# TREMONE.net
KiCad netlist of a schematic drawn in EAGLE
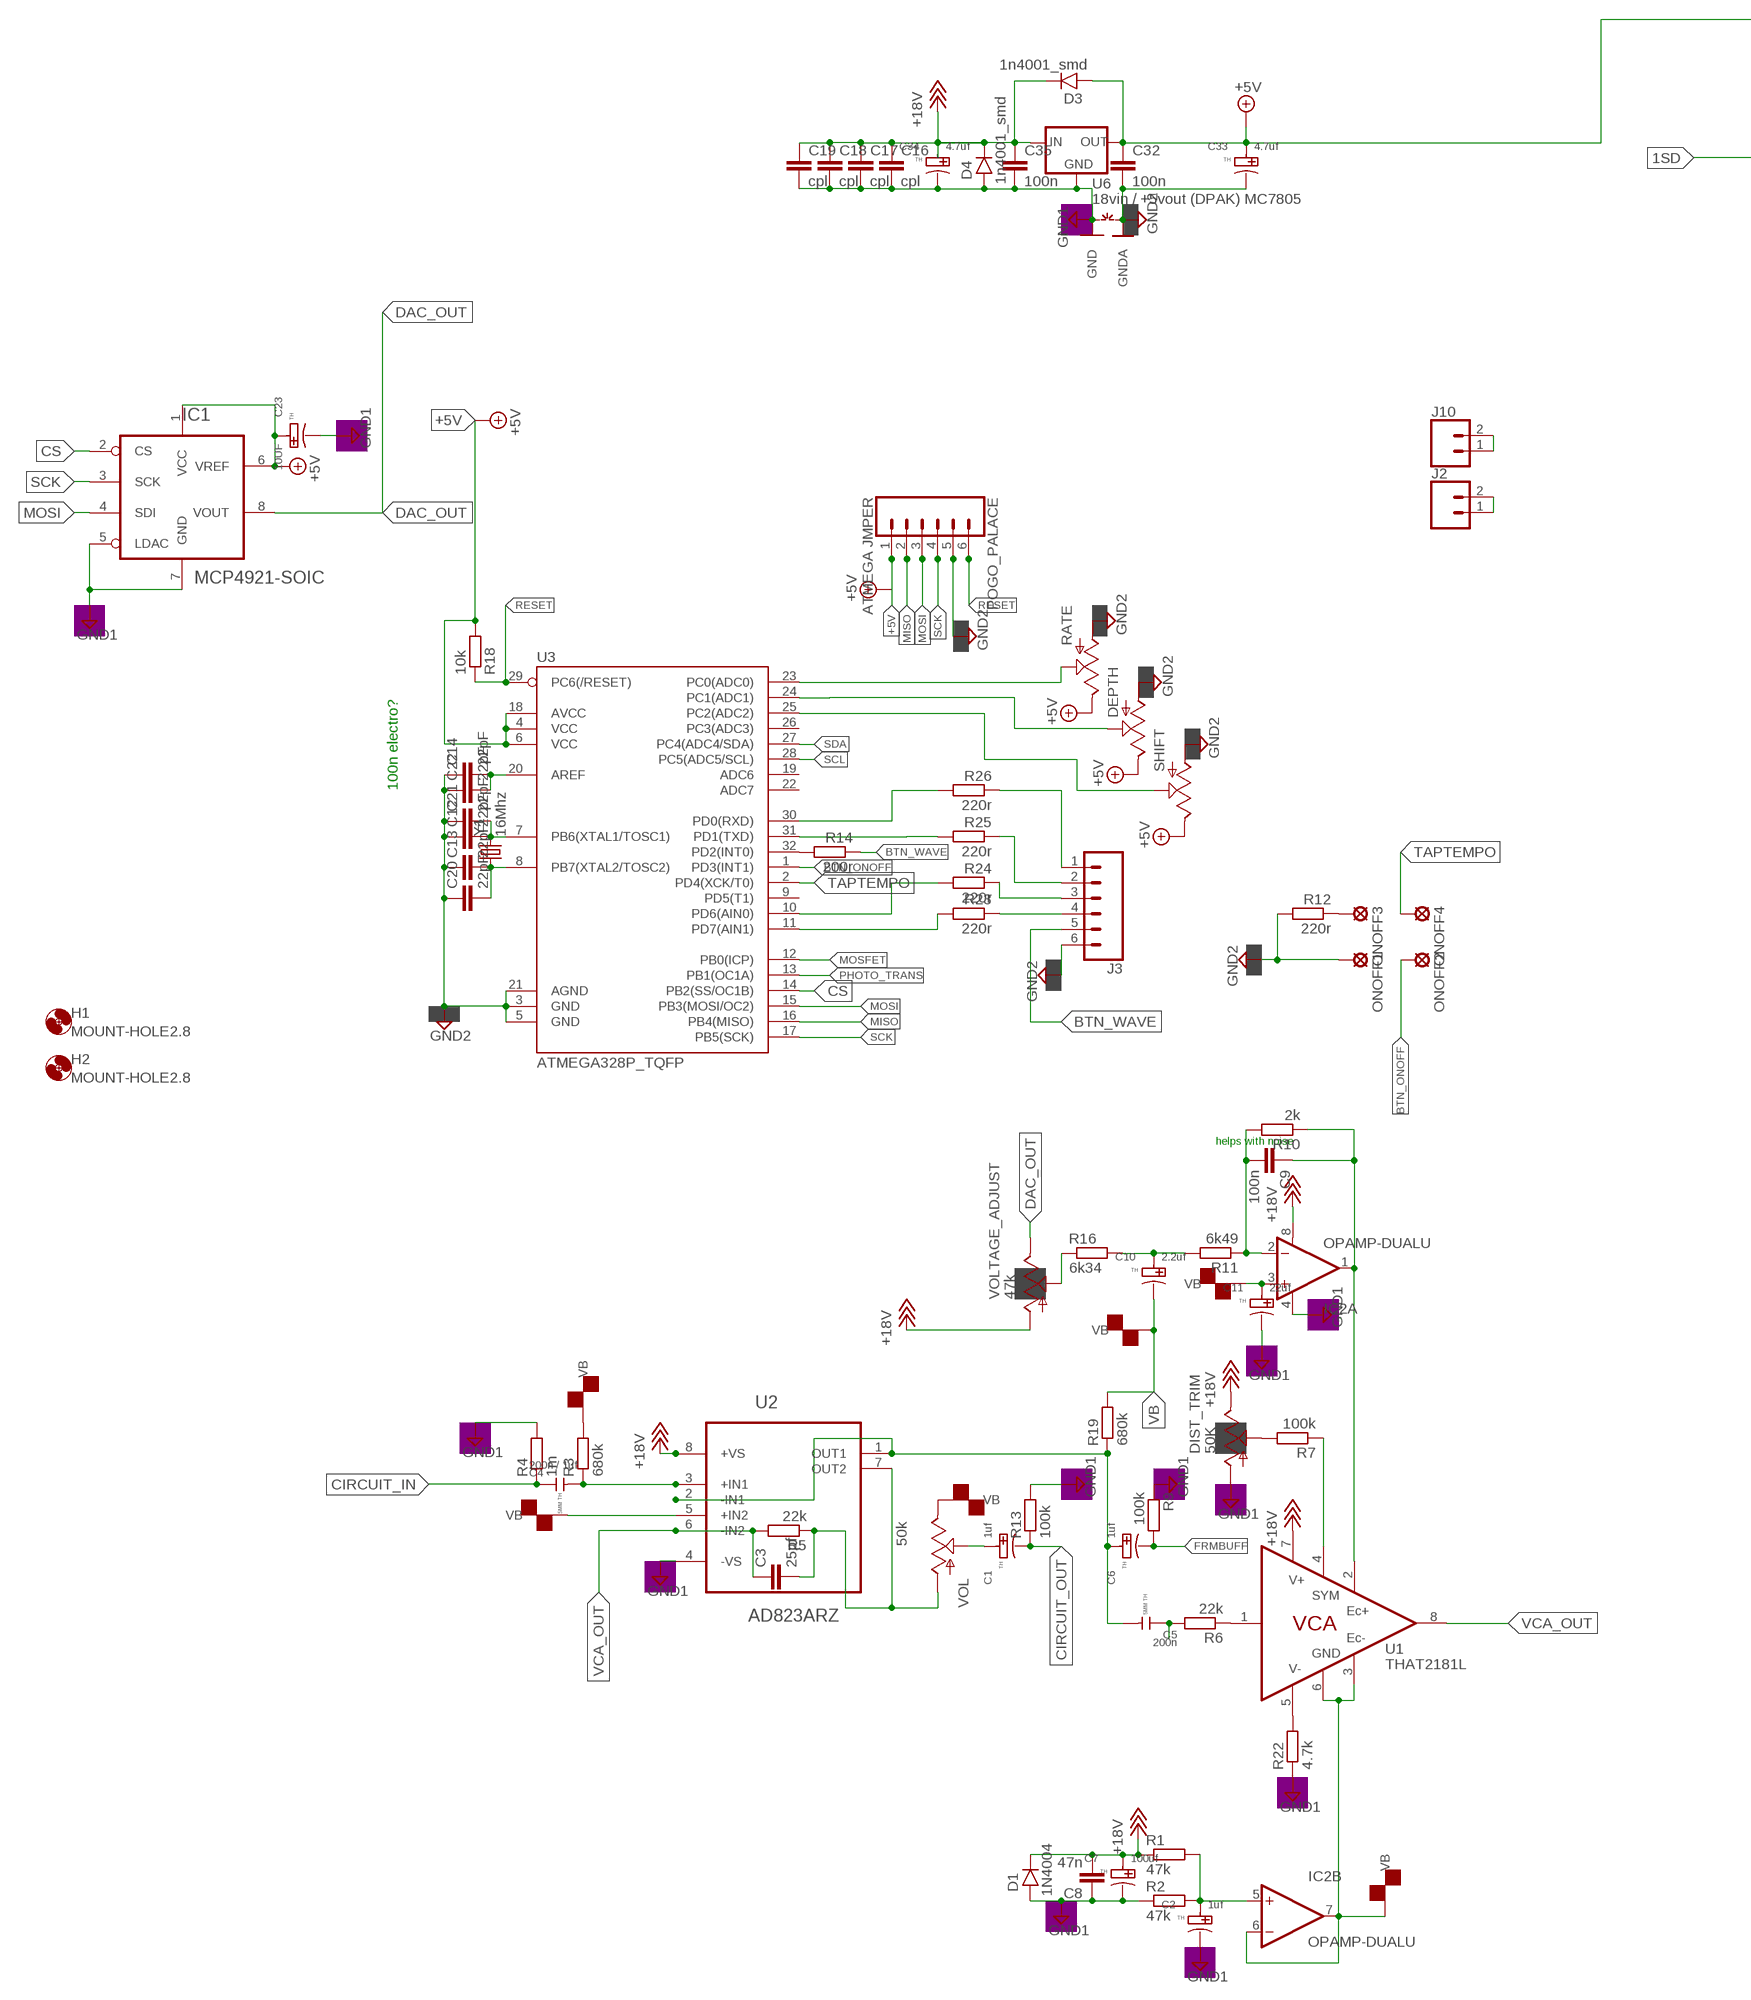
[diagram p0: schematic, sheet 1, part 1 of 2]
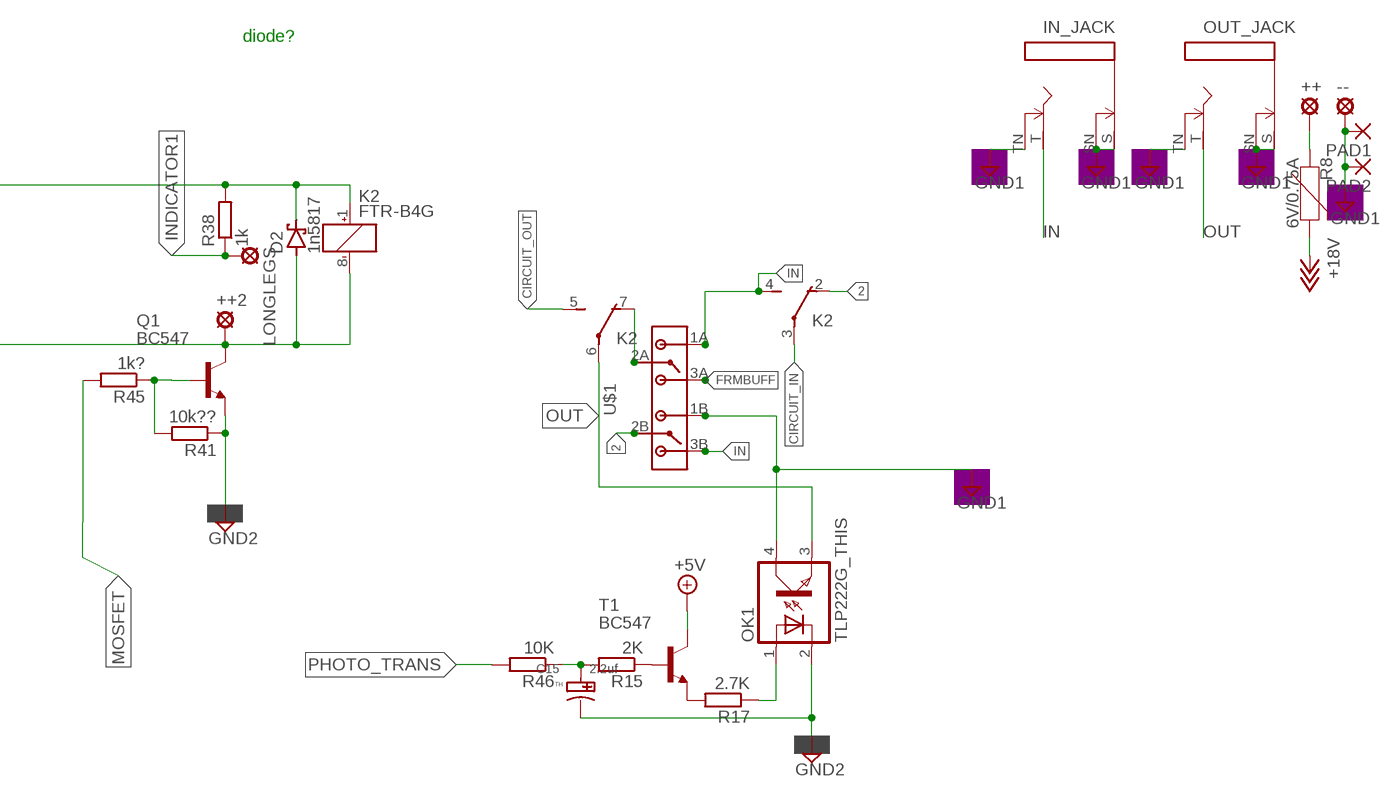
[diagram p1: schematic, sheet 1, part 2 of 2]

(export (version "E")
  (design (tool "Eeschema 10.0.6"))
  (components
    (comp (ref "++")
      (value "LSP10")
      (footprint "eagle-import:LSP10")
      (libsource (lib "eagle-import") (part "LSP10"))
    )
    (comp (ref "++2")
      (value "LSP10")
      (footprint "eagle-import:LSP10")
      (libsource (lib "eagle-import") (part "LSP10"))
    )
    (comp (ref "--")
      (value "LSP10")
      (footprint "eagle-import:LSP10")
      (libsource (lib "eagle-import") (part "LSP10"))
    )
    (comp (ref "C1")
      (value "1uf")
      (footprint "eagle-import:PC-D5.3MM")
      (fields (field (name "PACKAGE") "TH"))
      (libsource (lib "eagle-import") (part "THRU-HOLE-POLARIZED"))
    )
    (comp (ref "C2")
      (value "1uf")
      (footprint "eagle-import:PC-D5.3MM")
      (fields (field (name "PACKAGE") "TH"))
      (libsource (lib "eagle-import") (part "THRU-HOLE-POLARIZED"))
    )
    (comp (ref "C3")
      (value "25pf")
      (footprint "eagle-import:C1206")
      (libsource (lib "eagle-import") (part "C-EUC1206"))
    )
    (comp (ref "C4")
      (value "200n / 1uf")
      (footprint "eagle-import:CERAMIC-5MM")
      (fields (field (name "PACKAGE") "5MM TH"))
      (libsource (lib "eagle-import") (part "THRU_HOLE_5MM_SPACING"))
    )
    (comp (ref "C5")
      (value "200n")
      (footprint "eagle-import:CERAMIC-5MM")
      (fields (field (name "PACKAGE") "5MM TH"))
      (libsource (lib "eagle-import") (part "THRU_HOLE_5MM_SPACING"))
    )
    (comp (ref "C6")
      (value "1uf")
      (footprint "eagle-import:PC-D5.3MM")
      (fields (field (name "PACKAGE") "TH"))
      (libsource (lib "eagle-import") (part "THRU-HOLE-POLARIZED"))
    )
    (comp (ref "C7")
      (value "100uf")
      (footprint "eagle-import:PC-D5.3MM")
      (fields (field (name "PACKAGE") "TH"))
      (libsource (lib "eagle-import") (part "THRU-HOLE-POLARIZED"))
    )
    (comp (ref "C8")
      (value "47n")
      (footprint "eagle-import:C1206")
      (libsource (lib "eagle-import") (part "C-EUC1206"))
    )
    (comp (ref "C9")
      (value "100n")
      (footprint "eagle-import:C1206")
      (libsource (lib "eagle-import") (part "C-EUC1206"))
    )
    (comp (ref "C10")
      (value "2.2uf")
      (footprint "eagle-import:PC-D5.3MM")
      (fields (field (name "PACKAGE") "TH"))
      (libsource (lib "eagle-import") (part "THRU-HOLE-POLARIZED"))
    )
    (comp (ref "C11")
      (value "22uf")
      (footprint "eagle-import:PC-D5.3MM")
      (fields (field (name "PACKAGE") "TH"))
      (libsource (lib "eagle-import") (part "THRU-HOLE-POLARIZED"))
    )
    (comp (ref "C12")
      (value "22pF")
      (footprint "eagle-import:0603")
      (libsource (lib "eagle-import") (part "22PF-0603-50V-5%"))
    )
    (comp (ref "C13")
      (value "22pF")
      (footprint "eagle-import:0603")
      (libsource (lib "eagle-import") (part "22PF-0603-50V-5%"))
    )
    (comp (ref "C14")
      (value "22pF")
      (footprint "eagle-import:CAP-PTH-2.54")
      (libsource (lib "eagle-import") (part "22PF-PTH-2.54MM-200V-5%"))
    )
    (comp (ref "C15")
      (value "2.2uf")
      (footprint "eagle-import:PC-D5.3MM")
      (fields (field (name "PACKAGE") "TH"))
      (libsource (lib "eagle-import") (part "THRU-HOLE-POLARIZED"))
    )
    (comp (ref "C16")
      (value "cpl")
      (footprint "eagle-import:C1206")
      (libsource (lib "eagle-import") (part "resistor_348_C-EUC1206"))
    )
    (comp (ref "C17")
      (value "cpl")
      (footprint "eagle-import:C1206")
      (libsource (lib "eagle-import") (part "resistor_348_C-EUC1206"))
    )
    (comp (ref "C18")
      (value "cpl")
      (footprint "eagle-import:C1206")
      (libsource (lib "eagle-import") (part "resistor_348_C-EUC1206"))
    )
    (comp (ref "C19")
      (value "cpl")
      (footprint "eagle-import:C1206")
      (libsource (lib "eagle-import") (part "resistor_348_C-EUC1206"))
    )
    (comp (ref "C20")
      (value "22pF")
      (footprint "eagle-import:CAP-PTH-2.54")
      (libsource (lib "eagle-import") (part "22PF-PTH-2.54MM-200V-5%"))
    )
    (comp (ref "C21")
      (value "22pF")
      (footprint "eagle-import:CAP-PTH-2.54")
      (libsource (lib "eagle-import") (part "22PF-PTH-2.54MM-200V-5%"))
    )
    (comp (ref "C22")
      (value "22pF")
      (footprint "eagle-import:0603")
      (libsource (lib "eagle-import") (part "22PF-0603-50V-5%"))
    )
    (comp (ref "C23")
      (value "10UF")
      (footprint "eagle-import:PC-D5.3MM")
      (fields (field (name "PACKAGE") "TH"))
      (libsource (lib "eagle-import") (part "THRU-HOLE-POLARIZED"))
    )
    (comp (ref "C32")
      (value "100n")
      (footprint "eagle-import:C1206")
      (libsource (lib "eagle-import") (part "resistor_348_C-EUC1206"))
    )
    (comp (ref "C33")
      (value "4.7uf")
      (footprint "eagle-import:PC-D5.3MM")
      (fields (field (name "PACKAGE") "TH"))
      (libsource (lib "eagle-import") (part "THRU-HOLE-POLARIZED"))
    )
    (comp (ref "C34")
      (value "4.7uf")
      (footprint "eagle-import:PC-D5.3MM")
      (fields (field (name "PACKAGE") "TH"))
      (libsource (lib "eagle-import") (part "THRU-HOLE-POLARIZED"))
    )
    (comp (ref "C35")
      (value "100n")
      (footprint "eagle-import:C1206")
      (libsource (lib "eagle-import") (part "resistor_348_C-EUC1206"))
    )
    (comp (ref "D1")
      (value "1N4004")
      (footprint "eagle-import:DO41-1")
      (libsource (lib "eagle-import") (part "1N400X.1"))
    )
    (comp (ref "D2")
      (value "1n5817")
      (footprint "eagle-import:SMB")
      (libsource (lib "eagle-import") (part "SCHOTTKY-DIODESMD"))
    )
    (comp (ref "D3")
      (value "1n4001_smd")
      (footprint "eagle-import:DO41-1")
      (libsource (lib "eagle-import") (part "1N400X.1"))
    )
    (comp (ref "D4")
      (value "1n4001_smd")
      (footprint "eagle-import:DO41-1")
      (libsource (lib "eagle-import") (part "1N400X.1"))
    )
    (comp (ref "DEPTH")
      (value "POT")
      (footprint "eagle-import:ALPS_POT")
      (libsource (lib "eagle-import") (part "POT"))
    )
    (comp (ref "DIST_TRIM")
      (value "50K")
      (footprint "eagle-import:3223G")
      (libsource (lib "eagle-import") (part "TRIM_US-3223G"))
    )
    (comp (ref "H1")
      (value "MOUNT-HOLE2.8")
      (footprint "eagle-import:2,8")
      (libsource (lib "eagle-import") (part "MOUNT-HOLE2.8"))
    )
    (comp (ref "H2")
      (value "MOUNT-HOLE2.8")
      (footprint "eagle-import:2,8")
      (libsource (lib "eagle-import") (part "MOUNT-HOLE2.8"))
    )
    (comp (ref "IC1")
      (value "MCP4921-SOIC")
      (footprint "eagle-import:SOIC-8")
      (libsource (lib "eagle-import") (part "MCP491-SOIC2"))
    )
    (comp (ref "IC2")
      (value "OPAMP-DUALU")
      (footprint "eagle-import:SO08")
      (libsource (lib "eagle-import") (part "OPAMP-DUALU"))
    )
    (comp (ref "IN_JACK")
      (value "MMMONNNNOHOLES")
      (footprint "eagle-import:MONONOHOLES")
      (libsource (lib "eagle-import") (part "MMMONNNNOHOLES"))
    )
    (comp (ref "J2")
      (value "CONN_02PTH3")
      (footprint "eagle-import:1X02_LONGPADS")
      (libsource (lib "eagle-import") (part "CONN_02PTH3"))
    )
    (comp (ref "J3")
      (value "CONN_06NO_SILK_FEMALE_PTH")
      (footprint "eagle-import:1X06_NO_SILK")
      (libsource (lib "eagle-import") (part "CONN_06NO_SILK_FEMALE_PTH"))
    )
    (comp (ref "J10")
      (value "CONN_02PTH3")
      (footprint "eagle-import:1X02_LONGPADS")
      (libsource (lib "eagle-import") (part "CONN_02PTH3"))
    )
    (comp (ref "K2")
      (value "FTR-B4G")
      (footprint "eagle-import:FTR-B4G")
      (libsource (lib "eagle-import") (part "FTR-B4G"))
    )
    (comp (ref "LONGLEGS")
      (value "LSP10")
      (footprint "eagle-import:LSP10")
      (libsource (lib "eagle-import") (part "LSP10"))
    )
    (comp (ref "OK1")
      (value "TLP222G_THIS")
      (footprint "eagle-import:DIL04")
      (libsource (lib "eagle-import") (part "TLP222G_THIS"))
    )
    (comp (ref "ONOFF1")
      (value "LSP10")
      (footprint "eagle-import:LSP10")
      (libsource (lib "eagle-import") (part "LSP10"))
    )
    (comp (ref "ONOFF2")
      (value "LSP10")
      (footprint "eagle-import:LSP10")
      (libsource (lib "eagle-import") (part "LSP10"))
    )
    (comp (ref "ONOFF3")
      (value "LSP10")
      (footprint "eagle-import:LSP10")
      (libsource (lib "eagle-import") (part "LSP10"))
    )
    (comp (ref "ONOFF4")
      (value "LSP10")
      (footprint "eagle-import:LSP10")
      (libsource (lib "eagle-import") (part "LSP10"))
    )
    (comp (ref "OUT_JACK")
      (value "MMMONNNNOHOLES")
      (footprint "eagle-import:MONONOHOLES")
      (libsource (lib "eagle-import") (part "MMMONNNNOHOLES"))
    )
    (comp (ref "PAD1")
      (value "SMD5")
      (footprint "eagle-import:SMD2,54-5,08")
      (libsource (lib "eagle-import") (part "SMD5"))
    )
    (comp (ref "PAD2")
      (value "SMD5")
      (footprint "eagle-import:SMD2,54-5,08")
      (libsource (lib "eagle-import") (part "SMD5"))
    )
    (comp (ref "POGO_PALACE")
      (value "ATMEGA JMPER")
      (footprint "eagle-import:1X06_LONGPADS")
      (libsource (lib "eagle-import") (part "CONN_06LONGPADS"))
    )
    (comp (ref "Q1")
      (value "BC547")
      (footprint "eagle-import:TO92")
      (libsource (lib "eagle-import") (part "BC547"))
    )
    (comp (ref "R1")
      (value "47k")
      (footprint "eagle-import:M1206")
      (libsource (lib "eagle-import") (part "R-EU_M1206"))
    )
    (comp (ref "R2")
      (value "47k")
      (footprint "eagle-import:M1206")
      (libsource (lib "eagle-import") (part "R-EU_M1206"))
    )
    (comp (ref "R3")
      (value "680k")
      (footprint "eagle-import:M1206")
      (libsource (lib "eagle-import") (part "R-EU_M1206"))
    )
    (comp (ref "R4")
      (value "1m")
      (footprint "eagle-import:M1206")
      (libsource (lib "eagle-import") (part "R-EU_M1206"))
    )
    (comp (ref "R5")
      (value "22k")
      (footprint "eagle-import:M1206")
      (libsource (lib "eagle-import") (part "R-EU_M1206"))
    )
    (comp (ref "R6")
      (value "22k")
      (footprint "eagle-import:M1206")
      (libsource (lib "eagle-import") (part "R-EU_M1206"))
    )
    (comp (ref "R7")
      (value "100k")
      (footprint "eagle-import:M1206")
      (libsource (lib "eagle-import") (part "R-EU_M1206"))
    )
    (comp (ref "R8")
      (value "6V/0.75A")
      (footprint "eagle-import:1206")
      (libsource (lib "eagle-import") (part "PPTC_THREE-QUARTER-AMP"))
    )
    (comp (ref "R9")
      (value "100k")
      (footprint "eagle-import:M1206")
      (libsource (lib "eagle-import") (part "R-EU_M1206"))
    )
    (comp (ref "R10")
      (value "2k")
      (footprint "eagle-import:M1206")
      (libsource (lib "eagle-import") (part "R-EU_M1206"))
    )
    (comp (ref "R11")
      (value "6k49")
      (footprint "eagle-import:M1206")
      (libsource (lib "eagle-import") (part "R-EU_M1206"))
    )
    (comp (ref "R12")
      (value "220r")
      (footprint "eagle-import:M1206")
      (libsource (lib "eagle-import") (part "R-EU_M1206"))
    )
    (comp (ref "R13")
      (value "100k")
      (footprint "eagle-import:M1206")
      (libsource (lib "eagle-import") (part "R-EU_M1206"))
    )
    (comp (ref "R14")
      (value "200r")
      (footprint "eagle-import:M1206")
      (libsource (lib "eagle-import") (part "R-EU_M1206"))
    )
    (comp (ref "R15")
      (value "2K")
      (footprint "eagle-import:M1206")
      (libsource (lib "eagle-import") (part "resistor_348_R-EU_M1206"))
    )
    (comp (ref "R16")
      (value "6k34")
      (footprint "eagle-import:M1206")
      (libsource (lib "eagle-import") (part "R-EU_M1206"))
    )
    (comp (ref "R17")
      (value "2.7K")
      (footprint "eagle-import:M1206")
      (libsource (lib "eagle-import") (part "resistor_348_R-EU_M1206"))
    )
    (comp (ref "R18")
      (value "10k")
      (footprint "eagle-import:M1206")
      (libsource (lib "eagle-import") (part "R-EU_M1206"))
    )
    (comp (ref "R19")
      (value "680k")
      (footprint "eagle-import:M1206")
      (libsource (lib "eagle-import") (part "R-EU_M1206"))
    )
    (comp (ref "R22")
      (value "4.7k")
      (footprint "eagle-import:M1206")
      (libsource (lib "eagle-import") (part "R-EU_M1206"))
    )
    (comp (ref "R23")
      (value "220r")
      (footprint "eagle-import:M1206")
      (libsource (lib "eagle-import") (part "R-EU_M1206"))
    )
    (comp (ref "R24")
      (value "220r")
      (footprint "eagle-import:M1206")
      (libsource (lib "eagle-import") (part "R-EU_M1206"))
    )
    (comp (ref "R25")
      (value "220r")
      (footprint "eagle-import:M1206")
      (libsource (lib "eagle-import") (part "R-EU_M1206"))
    )
    (comp (ref "R26")
      (value "220r")
      (footprint "eagle-import:M1206")
      (libsource (lib "eagle-import") (part "R-EU_M1206"))
    )
    (comp (ref "R38")
      (value "1k")
      (footprint "eagle-import:M1206")
      (libsource (lib "eagle-import") (part "resistor_348_R-EU_M1206"))
    )
    (comp (ref "R41")
      (value "10k??")
      (footprint "eagle-import:M1206")
      (libsource (lib "eagle-import") (part "resistor_348_R-EU_M1206"))
    )
    (comp (ref "R45")
      (value "1k?")
      (footprint "eagle-import:M1206")
      (libsource (lib "eagle-import") (part "resistor_348_R-EU_M1206"))
    )
    (comp (ref "R46")
      (value "10K")
      (footprint "eagle-import:M1206")
      (libsource (lib "eagle-import") (part "resistor_348_R-EU_M1206"))
    )
    (comp (ref "RATE")
      (value "POT")
      (footprint "eagle-import:ALPS_POT")
      (libsource (lib "eagle-import") (part "POT"))
    )
    (comp (ref "SHIFT")
      (value "POT")
      (footprint "eagle-import:ALPS_POT")
      (libsource (lib "eagle-import") (part "POT"))
    )
    (comp (ref "T1")
      (value "BC547")
      (footprint "eagle-import:TO92")
      (libsource (lib "eagle-import") (part "transistor_402_BC547"))
    )
    (comp (ref "U$1")
      (value "BYSWITCH")
      (footprint "eagle-import:BUFF_TRBYPASS")
      (libsource (lib "eagle-import") (part "BYSWITCH"))
    )
    (comp (ref "U1")
      (value "THAT2181L")
      (footprint "eagle-import:SIP8")
      (libsource (lib "eagle-import") (part "THAT2181L"))
    )
    (comp (ref "U2")
      (value "AD823ARZ")
      (footprint "eagle-import:SOIC127P600X175-8N")
      (libsource (lib "eagle-import") (part "AD823ARZ"))
    )
    (comp (ref "U3")
      (value "ATMEGA328P_TQFP")
      (footprint "eagle-import:TQFP32-08")
      (libsource (lib "eagle-import") (part "ATMEGA328P_TQFP"))
    )
    (comp (ref "U6")
      (value "18vin / +5vout (DPAK) MC7805")
      (footprint "eagle-import:TO-252")
      (libsource (lib "eagle-import") (part "V_REG_78XX7812"))
    )
    (comp (ref "VOL")
      (value "50k")
      (footprint "eagle-import:ALPS_POT")
      (libsource (lib "eagle-import") (part "POT"))
    )
    (comp (ref "VOLTAGE_ADJUST")
      (value "47k")
      (footprint "eagle-import:3223G")
      (libsource (lib "eagle-import") (part "TRIM_US-3223G"))
    )
    (comp (ref "Y1")
      (value "16Mhz")
      (footprint "eagle-import:HC49US")
      (libsource (lib "eagle-import") (part "CRYSTALHC49US"))
    )
    (comp (ref "~NUDEV~1")
      (value "GND-GNDA1,27MM")
      (footprint "eagle-import:GND-GNDA-1,27MM")
      (libsource (lib "eagle-import") (part "GND-GNDA1,27MM"))
    )
  )
  (nets
    (net (code "1") (name "+5V") (class "Default")
      (node (ref "C23") (pin "+") (pinfunction "+_+") (pintype "passive"))
      (node (ref "C32") (pin "1") (pinfunction "1_1") (pintype "passive"))
      (node (ref "C33") (pin "+") (pinfunction "+_+") (pintype "passive"))
      (node (ref "D2") (pin "C") (pinfunction "C_C") (pintype "passive"))
      (node (ref "D3") (pin "A") (pinfunction "A_A") (pintype "passive"))
      (node (ref "DEPTH") (pin "P$1") (pinfunction "E_P$1") (pintype "passive"))
      (node (ref "IC1") (pin "1") (pinfunction "VCC_1") (pintype "power_in"))
      (node (ref "IC1") (pin "6") (pinfunction "VREF_6") (pintype "input"))
      (node (ref "K2") (pin "1") (pinfunction "+_1") (pintype "passive"))
      (node (ref "POGO_PALACE") (pin "1") (pinfunction "1_1") (pintype "passive"))
      (node (ref "R18") (pin "2") (pinfunction "2_2") (pintype "passive"))
      (node (ref "R38") (pin "2") (pinfunction "2_2") (pintype "passive"))
      (node (ref "RATE") (pin "P$1") (pinfunction "E_P$1") (pintype "passive"))
      (node (ref "SHIFT") (pin "P$1") (pinfunction "E_P$1") (pintype "passive"))
      (node (ref "T1") (pin "3") (pinfunction "C_3") (pintype "passive"))
      (node (ref "U3") (pin "18") (pinfunction "AVCC_18") (pintype "bidirectional"))
      (node (ref "U3") (pin "4") (pinfunction "VCC_4") (pintype "bidirectional"))
      (node (ref "U3") (pin "6") (pinfunction "VCC_6") (pintype "bidirectional"))
      (node (ref "U6") (pin "2") (pinfunction "OUT_2") (pintype "passive"))
    )
    (net (code "2") (name "+18V") (class "Default")
      (node (ref "C16") (pin "1") (pinfunction "1_1") (pintype "passive"))
      (node (ref "C17") (pin "1") (pinfunction "1_1") (pintype "passive"))
      (node (ref "C18") (pin "1") (pinfunction "1_1") (pintype "passive"))
      (node (ref "C19") (pin "1") (pinfunction "1_1") (pintype "passive"))
      (node (ref "C34") (pin "+") (pinfunction "+_+") (pintype "passive"))
      (node (ref "C35") (pin "1") (pinfunction "1_1") (pintype "passive"))
      (node (ref "C7") (pin "+") (pinfunction "+_+") (pintype "passive"))
      (node (ref "C8") (pin "2") (pinfunction "2_2") (pintype "passive"))
      (node (ref "D1") (pin "C") (pinfunction "C_C") (pintype "passive"))
      (node (ref "D3") (pin "C") (pinfunction "C_C") (pintype "passive"))
      (node (ref "D4") (pin "C") (pinfunction "C_C") (pintype "passive"))
      (node (ref "DIST_TRIM") (pin "3") (pinfunction "E_3") (pintype "passive"))
      (node (ref "IC2") (pin "8") (pinfunction "V+_8") (pintype "power_in"))
      (node (ref "R1") (pin "1") (pinfunction "1_1") (pintype "passive"))
      (node (ref "R8") (pin "2") (pinfunction "2_2") (pintype "bidirectional"))
      (node (ref "U1") (pin "7") (pinfunction "V+_7") (pintype "power_in"))
      (node (ref "U2") (pin "8") (pinfunction "+VS_8") (pintype "power_in"))
      (node (ref "U6") (pin "1") (pinfunction "IN_1") (pintype "input"))
      (node (ref "VOLTAGE_ADJUST") (pin "1") (pinfunction "A_1") (pintype "passive"))
    )
    (net (code "3") (name "1SD") (class "Default")
      (node (ref "++2") (pin "MP") (pinfunction "MP_MP") (pintype "passive"))
      (node (ref "D2") (pin "A") (pinfunction "A_A") (pintype "passive"))
      (node (ref "K2") (pin "8") (pinfunction "-_8") (pintype "passive"))
      (node (ref "Q1") (pin "3") (pinfunction "C_3") (pintype "passive"))
    )
    (net (code "4") (name "2") (class "Default")
      (node (ref "K2") (pin "2") (pinfunction "O_2") (pintype "passive"))
      (node (ref "U$1") (pin "2B") (pinfunction "2B_2B") (pintype "passive"))
    )
    (net (code "5") (name "BTN_ONOFF") (class "Default")
      (node (ref "ONOFF2") (pin "MP") (pinfunction "MP_MP") (pintype "passive"))
      (node (ref "U3") (pin "1") (pinfunction "PD3(INT1)_1") (pintype "bidirectional"))
    )
    (net (code "6") (name "BTN_WAVE") (class "Default")
      (node (ref "J3") (pin "5") (pinfunction "5_5") (pintype "passive"))
      (node (ref "R14") (pin "1") (pinfunction "1_1") (pintype "passive"))
    )
    (net (code "7") (name "CIRCUIT_IN") (class "Default")
      (node (ref "C4") (pin "1") (pinfunction "1_1") (pintype "passive"))
      (node (ref "K2") (pin "3") (pinfunction "P_3") (pintype "passive"))
      (node (ref "R4") (pin "1") (pinfunction "1_1") (pintype "passive"))
    )
    (net (code "8") (name "CIRCUIT_OUT") (class "Default")
      (node (ref "C1") (pin "-") (pinfunction "-_-") (pintype "passive"))
      (node (ref "K2") (pin "5") (pinfunction "S_5") (pintype "passive"))
      (node (ref "R13") (pin "1") (pinfunction "1_1") (pintype "passive"))
    )
    (net (code "9") (name "CS") (class "Default")
      (node (ref "IC1") (pin "2") (pinfunction "CS_2") (pintype "input"))
      (node (ref "U3") (pin "14") (pinfunction "PB2(SS/OC1B)_14") (pintype "bidirectional"))
    )
    (net (code "10") (name "DAC_OUT") (class "Default")
      (node (ref "IC1") (pin "8") (pinfunction "VOUT_8") (pintype "output"))
      (node (ref "VOLTAGE_ADJUST") (pin "3") (pinfunction "E_3") (pintype "passive"))
    )
    (net (code "11") (name "FRMBUFF") (class "Default")
      (node (ref "C6") (pin "-") (pinfunction "-_-") (pintype "passive"))
      (node (ref "R9") (pin "2") (pinfunction "2_2") (pintype "passive"))
      (node (ref "U$1") (pin "3A") (pinfunction "3A_3A") (pintype "passive"))
    )
    (net (code "12") (name "GND1") (class "Default")
      (node (ref "--") (pin "MP") (pinfunction "MP_MP") (pintype "passive"))
      (node (ref "C11") (pin "-") (pinfunction "-_-") (pintype "passive"))
      (node (ref "C16") (pin "2") (pinfunction "2_2") (pintype "passive"))
      (node (ref "C17") (pin "2") (pinfunction "2_2") (pintype "passive"))
      (node (ref "C18") (pin "2") (pinfunction "2_2") (pintype "passive"))
      (node (ref "C19") (pin "2") (pinfunction "2_2") (pintype "passive"))
      (node (ref "C2") (pin "-") (pinfunction "-_-") (pintype "passive"))
      (node (ref "C23") (pin "-") (pinfunction "-_-") (pintype "passive"))
      (node (ref "C34") (pin "-") (pinfunction "-_-") (pintype "passive"))
      (node (ref "C35") (pin "2") (pinfunction "2_2") (pintype "passive"))
      (node (ref "C7") (pin "-") (pinfunction "-_-") (pintype "passive"))
      (node (ref "C8") (pin "1") (pinfunction "1_1") (pintype "passive"))
      (node (ref "D1") (pin "A") (pinfunction "A_A") (pintype "passive"))
      (node (ref "D4") (pin "A") (pinfunction "A_A") (pintype "passive"))
      (node (ref "DIST_TRIM") (pin "1") (pinfunction "A_1") (pintype "passive"))
      (node (ref "IC1") (pin "5") (pinfunction "LDAC_5") (pintype "input"))
      (node (ref "IC1") (pin "7") (pinfunction "GND_7") (pintype "power_in"))
      (node (ref "IC2") (pin "4") (pinfunction "V-_4") (pintype "power_in"))
      (node (ref "IN_JACK") (pin "S") (pinfunction "S_S") (pintype "passive"))
      (node (ref "IN_JACK") (pin "SN") (pinfunction "SN_SN") (pintype "passive"))
      (node (ref "IN_JACK") (pin "TN") (pinfunction "TN_TN") (pintype "passive"))
      (node (ref "OK1") (pin "4") (pinfunction "COL_4") (pintype "passive"))
      (node (ref "OUT_JACK") (pin "S") (pinfunction "S_S") (pintype "passive"))
      (node (ref "OUT_JACK") (pin "SN") (pinfunction "SN_SN") (pintype "passive"))
      (node (ref "OUT_JACK") (pin "TN") (pinfunction "TN_TN") (pintype "passive"))
      (node (ref "PAD1") (pin "1") (pinfunction "P_1") (pintype "passive"))
      (node (ref "PAD2") (pin "1") (pinfunction "P_1") (pintype "passive"))
      (node (ref "R13") (pin "2") (pinfunction "2_2") (pintype "passive"))
      (node (ref "R2") (pin "1") (pinfunction "1_1") (pintype "passive"))
      (node (ref "R22") (pin "1") (pinfunction "1_1") (pintype "passive"))
      (node (ref "R4") (pin "2") (pinfunction "2_2") (pintype "passive"))
      (node (ref "R9") (pin "1") (pinfunction "1_1") (pintype "passive"))
      (node (ref "U$1") (pin "1B") (pinfunction "1B_1B") (pintype "passive"))
      (node (ref "U2") (pin "4") (pinfunction "-VS_4") (pintype "power_in"))
      (node (ref "U6") (pin "3") (pinfunction "GND_3") (pintype "input"))
      (node (ref "~NUDEV~1") (pin "GND") (pinfunction "GND_GND") (pintype "power_in"))
    )
    (net (code "13") (name "GND2") (class "Default")
      (node (ref "C12") (pin "1") (pinfunction "1_1") (pintype "passive"))
      (node (ref "C13") (pin "1") (pinfunction "1_1") (pintype "passive"))
      (node (ref "C14") (pin "1") (pinfunction "1_1") (pintype "passive"))
      (node (ref "C15") (pin "-") (pinfunction "-_-") (pintype "passive"))
      (node (ref "C20") (pin "1") (pinfunction "1_1") (pintype "passive"))
      (node (ref "C21") (pin "1") (pinfunction "1_1") (pintype "passive"))
      (node (ref "C22") (pin "1") (pinfunction "1_1") (pintype "passive"))
      (node (ref "C32") (pin "2") (pinfunction "2_2") (pintype "passive"))
      (node (ref "C33") (pin "-") (pinfunction "-_-") (pintype "passive"))
      (node (ref "DEPTH") (pin "P$3") (pinfunction "A_P$3") (pintype "passive"))
      (node (ref "J3") (pin "6") (pinfunction "6_6") (pintype "passive"))
      (node (ref "OK1") (pin "2") (pinfunction "C_2") (pintype "passive"))
      (node (ref "ONOFF1") (pin "MP") (pinfunction "MP_MP") (pintype "passive"))
      (node (ref "POGO_PALACE") (pin "5") (pinfunction "5_5") (pintype "passive"))
      (node (ref "Q1") (pin "1") (pinfunction "E_1") (pintype "passive"))
      (node (ref "R12") (pin "2") (pinfunction "2_2") (pintype "passive"))
      (node (ref "R41") (pin "1") (pinfunction "1_1") (pintype "passive"))
      (node (ref "RATE") (pin "P$3") (pinfunction "A_P$3") (pintype "passive"))
      (node (ref "SHIFT") (pin "P$3") (pinfunction "A_P$3") (pintype "passive"))
      (node (ref "U3") (pin "21") (pinfunction "AGND_21") (pintype "bidirectional"))
      (node (ref "U3") (pin "3") (pinfunction "GND_3") (pintype "bidirectional"))
      (node (ref "U3") (pin "5") (pinfunction "GND_5") (pintype "bidirectional"))
      (node (ref "~NUDEV~1") (pin "GNDA") (pinfunction "GNDA_GNDA") (pintype "power_in"))
    )
    (net (code "14") (name "IN") (class "Default")
      (node (ref "IN_JACK") (pin "T") (pinfunction "T_T") (pintype "passive"))
      (node (ref "K2") (pin "4") (pinfunction "S_4") (pintype "passive"))
      (node (ref "U$1") (pin "1A") (pinfunction "1A_1A") (pintype "passive"))
      (node (ref "U$1") (pin "3B") (pinfunction "3B_3B") (pintype "passive"))
    )
    (net (code "15") (name "INDICATOR1") (class "Default")
      (node (ref "LONGLEGS") (pin "MP") (pinfunction "MP_MP") (pintype "passive"))
      (node (ref "R38") (pin "1") (pinfunction "1_1") (pintype "passive"))
    )
    (net (code "16") (name "MISO") (class "Default")
      (node (ref "POGO_PALACE") (pin "2") (pinfunction "2_2") (pintype "passive"))
      (node (ref "U3") (pin "16") (pinfunction "PB4(MISO)_16") (pintype "bidirectional"))
    )
    (net (code "17") (name "MOSFET") (class "Default")
      (node (ref "R45") (pin "2") (pinfunction "2_2") (pintype "passive"))
      (node (ref "U3") (pin "12") (pinfunction "PB0(ICP)_12") (pintype "bidirectional"))
    )
    (net (code "18") (name "MOSI") (class "Default")
      (node (ref "IC1") (pin "4") (pinfunction "SDI_4") (pintype "input"))
      (node (ref "POGO_PALACE") (pin "3") (pinfunction "3_3") (pintype "passive"))
      (node (ref "U3") (pin "15") (pinfunction "PB3(MOSI/OC2)_15") (pintype "bidirectional"))
    )
    (net (code "19") (name "Net-(++-PadMP)") (class "Default")
      (node (ref "++") (pin "MP") (pinfunction "MP_MP") (pintype "passive"))
      (node (ref "R8") (pin "1") (pinfunction "1_1") (pintype "bidirectional"))
    )
    (net (code "20") (name "Net-(C5-Pad1)") (class "Default")
      (node (ref "C5") (pin "1") (pinfunction "1_1") (pintype "passive"))
      (node (ref "R6") (pin "2") (pinfunction "2_2") (pintype "passive"))
    )
    (net (code "21") (name "Net-(C10-Pad+)") (class "Default")
      (node (ref "C10") (pin "+") (pinfunction "+_+") (pintype "passive"))
      (node (ref "R11") (pin "2") (pinfunction "2_2") (pintype "passive"))
      (node (ref "R16") (pin "2") (pinfunction "2_2") (pintype "passive"))
    )
    (net (code "22") (name "Net-(C15-Pad+)") (class "Default")
      (node (ref "C15") (pin "+") (pinfunction "+_+") (pintype "passive"))
      (node (ref "R15") (pin "2") (pinfunction "2_2") (pintype "passive"))
      (node (ref "R46") (pin "1") (pinfunction "1_1") (pintype "passive"))
    )
    (net (code "23") (name "Net-(DEPTH-S)") (class "Default")
      (node (ref "DEPTH") (pin "P$2") (pinfunction "S_P$2") (pintype "passive"))
      (node (ref "U3") (pin "24") (pinfunction "PC1(ADC1)_24") (pintype "bidirectional"))
    )
    (net (code "24") (name "Net-(DIST_TRIM-S)") (class "Default")
      (node (ref "DIST_TRIM") (pin "2") (pinfunction "S_2") (pintype "passive"))
      (node (ref "R7") (pin "2") (pinfunction "2_2") (pintype "passive"))
    )
    (net (code "25") (name "Net-(IC2A--IN)") (class "Default")
      (node (ref "C9") (pin "2") (pinfunction "2_2") (pintype "passive"))
      (node (ref "IC2") (pin "2") (pinfunction "-IN_2") (pintype "input"))
      (node (ref "R10") (pin "2") (pinfunction "2_2") (pintype "passive"))
      (node (ref "R11") (pin "1") (pinfunction "1_1") (pintype "passive"))
    )
    (net (code "26") (name "Net-(IC2A-OUT)") (class "Default")
      (node (ref "C9") (pin "1") (pinfunction "1_1") (pintype "passive"))
      (node (ref "IC2") (pin "1") (pinfunction "OUT_1") (pintype "output"))
      (node (ref "R10") (pin "1") (pinfunction "1_1") (pintype "passive"))
      (node (ref "U1") (pin "2") (pinfunction "EC+_2") (pintype "passive"))
    )
    (net (code "27") (name "Net-(IC2B-+IN)") (class "Default")
      (node (ref "C2") (pin "+") (pinfunction "+_+") (pintype "passive"))
      (node (ref "IC2") (pin "5") (pinfunction "+IN_5") (pintype "input"))
      (node (ref "R1") (pin "2") (pinfunction "2_2") (pintype "passive"))
      (node (ref "R2") (pin "2") (pinfunction "2_2") (pintype "passive"))
    )
    (net (code "28") (name "Net-(J2-Pad1)") (class "Default")
      (node (ref "J2") (pin "1") (pinfunction "1_1") (pintype "passive"))
      (node (ref "J2") (pin "2") (pinfunction "2_2") (pintype "passive"))
    )
    (net (code "29") (name "Net-(J3-Pad1)") (class "Default")
      (node (ref "J3") (pin "1") (pinfunction "1_1") (pintype "passive"))
      (node (ref "R26") (pin "1") (pinfunction "1_1") (pintype "passive"))
    )
    (net (code "30") (name "Net-(J3-Pad2)") (class "Default")
      (node (ref "J3") (pin "2") (pinfunction "2_2") (pintype "passive"))
      (node (ref "R25") (pin "1") (pinfunction "1_1") (pintype "passive"))
    )
    (net (code "31") (name "Net-(J3-Pad3)") (class "Default")
      (node (ref "J3") (pin "3") (pinfunction "3_3") (pintype "passive"))
      (node (ref "R24") (pin "1") (pinfunction "1_1") (pintype "passive"))
    )
    (net (code "32") (name "Net-(J3-Pad4)") (class "Default")
      (node (ref "J3") (pin "4") (pinfunction "4_4") (pintype "passive"))
      (node (ref "R23") (pin "1") (pinfunction "1_1") (pintype "passive"))
    )
    (net (code "33") (name "Net-(J10-Pad1)") (class "Default")
      (node (ref "J10") (pin "1") (pinfunction "1_1") (pintype "passive"))
      (node (ref "J10") (pin "2") (pinfunction "2_2") (pintype "passive"))
    )
    (net (code "34") (name "Net-(K2B-O)") (class "Default")
      (node (ref "K2") (pin "7") (pinfunction "O_7") (pintype "passive"))
      (node (ref "U$1") (pin "2A") (pinfunction "2A_2A") (pintype "passive"))
    )
    (net (code "35") (name "Net-(OK1-A)") (class "Default")
      (node (ref "OK1") (pin "1") (pinfunction "A_1") (pintype "passive"))
      (node (ref "R17") (pin "1") (pinfunction "1_1") (pintype "passive"))
    )
    (net (code "36") (name "Net-(ONOFF3-PadMP)") (class "Default")
      (node (ref "ONOFF3") (pin "MP") (pinfunction "MP_MP") (pintype "passive"))
      (node (ref "R12") (pin "1") (pinfunction "1_1") (pintype "passive"))
    )
    (net (code "37") (name "Net-(Q1-B)") (class "Default")
      (node (ref "Q1") (pin "2") (pinfunction "B_2") (pintype "passive"))
      (node (ref "R41") (pin "2") (pinfunction "2_2") (pintype "passive"))
      (node (ref "R45") (pin "1") (pinfunction "1_1") (pintype "passive"))
    )
    (net (code "38") (name "Net-(RATE-S)") (class "Default")
      (node (ref "RATE") (pin "P$2") (pinfunction "S_P$2") (pintype "passive"))
      (node (ref "U3") (pin "23") (pinfunction "PC0(ADC0)_23") (pintype "bidirectional"))
    )
    (net (code "39") (name "Net-(SHIFT-S)") (class "Default")
      (node (ref "SHIFT") (pin "P$2") (pinfunction "S_P$2") (pintype "passive"))
      (node (ref "U3") (pin "25") (pinfunction "PC2(ADC2)_25") (pintype "bidirectional"))
    )
    (net (code "40") (name "Net-(T1-B)") (class "Default")
      (node (ref "R15") (pin "1") (pinfunction "1_1") (pintype "passive"))
      (node (ref "T1") (pin "2") (pinfunction "B_2") (pintype "passive"))
    )
    (net (code "41") (name "Net-(T1-E)") (class "Default")
      (node (ref "R17") (pin "2") (pinfunction "2_2") (pintype "passive"))
      (node (ref "T1") (pin "1") (pinfunction "E_1") (pintype "passive"))
    )
    (net (code "42") (name "Net-(U1-IN)") (class "Default")
      (node (ref "R6") (pin "1") (pinfunction "1_1") (pintype "passive"))
      (node (ref "U1") (pin "1") (pinfunction "IN_1") (pintype "input"))
    )
    (net (code "43") (name "Net-(U1-SYM)") (class "Default")
      (node (ref "R7") (pin "1") (pinfunction "1_1") (pintype "passive"))
      (node (ref "U1") (pin "4") (pinfunction "SYM_4") (pintype "passive"))
    )
    (net (code "44") (name "Net-(U1-V-)") (class "Default")
      (node (ref "R22") (pin "2") (pinfunction "2_2") (pintype "passive"))
      (node (ref "U1") (pin "5") (pinfunction "V-_5") (pintype "power_in"))
    )
    (net (code "45") (name "Net-(U2-+IN1)") (class "Default")
      (node (ref "C4") (pin "2") (pinfunction "2_2") (pintype "passive"))
      (node (ref "R3") (pin "1") (pinfunction "1_1") (pintype "passive"))
      (node (ref "U2") (pin "3") (pinfunction "+IN1_3") (pintype "input"))
    )
    (net (code "46") (name "Net-(U2--IN1)") (class "Default")
      (node (ref "C5") (pin "2") (pinfunction "2_2") (pintype "passive"))
      (node (ref "C6") (pin "+") (pinfunction "+_+") (pintype "passive"))
      (node (ref "R19") (pin "1") (pinfunction "1_1") (pintype "passive"))
      (node (ref "U2") (pin "1") (pinfunction "OUT1_1") (pintype "output"))
      (node (ref "U2") (pin "2") (pinfunction "-IN1_2") (pintype "input"))
    )
    (net (code "47") (name "Net-(U2-OUT2)") (class "Default")
      (node (ref "C3") (pin "2") (pinfunction "2_2") (pintype "passive"))
      (node (ref "R5") (pin "1") (pinfunction "1_1") (pintype "passive"))
      (node (ref "U2") (pin "7") (pinfunction "OUT2_7") (pintype "output"))
      (node (ref "VOL") (pin "P$3") (pinfunction "A_P$3") (pintype "passive"))
    )
    (net (code "48") (name "Net-(U3-AREF)") (class "Default")
      (node (ref "C14") (pin "2") (pinfunction "2_2") (pintype "passive"))
      (node (ref "C22") (pin "2") (pinfunction "2_2") (pintype "passive"))
      (node (ref "U3") (pin "20") (pinfunction "AREF_20") (pintype "bidirectional"))
    )
    (net (code "49") (name "Net-(U3-PB6(XTAL1{slash}TOSC1))") (class "Default")
      (node (ref "C12") (pin "2") (pinfunction "2_2") (pintype "passive"))
      (node (ref "C21") (pin "2") (pinfunction "2_2") (pintype "passive"))
      (node (ref "U3") (pin "7") (pinfunction "PB6(XTAL1/TOSC1)_7") (pintype "bidirectional"))
      (node (ref "Y1") (pin "2") (pinfunction "2_2") (pintype "passive"))
    )
    (net (code "50") (name "Net-(U3-PB7(XTAL2{slash}TOSC2))") (class "Default")
      (node (ref "C13") (pin "2") (pinfunction "2_2") (pintype "passive"))
      (node (ref "C20") (pin "2") (pinfunction "2_2") (pintype "passive"))
      (node (ref "U3") (pin "8") (pinfunction "PB7(XTAL2/TOSC2)_8") (pintype "bidirectional"))
      (node (ref "Y1") (pin "1") (pinfunction "1_1") (pintype "passive"))
    )
    (net (code "51") (name "Net-(U3-PD0(RXD))") (class "Default")
      (node (ref "R26") (pin "2") (pinfunction "2_2") (pintype "passive"))
      (node (ref "U3") (pin "30") (pinfunction "PD0(RXD)_30") (pintype "bidirectional"))
    )
    (net (code "52") (name "Net-(U3-PD1(TXD))") (class "Default")
      (node (ref "R25") (pin "2") (pinfunction "2_2") (pintype "passive"))
      (node (ref "U3") (pin "31") (pinfunction "PD1(TXD)_31") (pintype "bidirectional"))
    )
    (net (code "53") (name "Net-(U3-PD2(INT0))") (class "Default")
      (node (ref "R14") (pin "2") (pinfunction "2_2") (pintype "passive"))
      (node (ref "U3") (pin "32") (pinfunction "PD2(INT0)_32") (pintype "bidirectional"))
    )
    (net (code "54") (name "Net-(U3-PD6(AIN0))") (class "Default")
      (node (ref "R24") (pin "2") (pinfunction "2_2") (pintype "passive"))
      (node (ref "U3") (pin "10") (pinfunction "PD6(AIN0)_10") (pintype "bidirectional"))
    )
    (net (code "55") (name "Net-(U3-PD7(AIN1))") (class "Default")
      (node (ref "R23") (pin "2") (pinfunction "2_2") (pintype "passive"))
      (node (ref "U3") (pin "11") (pinfunction "PD7(AIN1)_11") (pintype "bidirectional"))
    )
    (net (code "56") (name "Net-(VOL-S)") (class "Default")
      (node (ref "C1") (pin "+") (pinfunction "+_+") (pintype "passive"))
      (node (ref "VOL") (pin "P$2") (pinfunction "S_P$2") (pintype "passive"))
    )
    (net (code "57") (name "Net-(VOLTAGE_ADJUST-S)") (class "Default")
      (node (ref "R16") (pin "1") (pinfunction "1_1") (pintype "passive"))
      (node (ref "VOLTAGE_ADJUST") (pin "2") (pinfunction "S_2") (pintype "passive"))
    )
    (net (code "58") (name "OUT") (class "Default")
      (node (ref "K2") (pin "6") (pinfunction "P_6") (pintype "passive"))
      (node (ref "OK1") (pin "3") (pinfunction "EMIT_3") (pintype "passive"))
      (node (ref "OUT_JACK") (pin "T") (pinfunction "T_T") (pintype "passive"))
    )
    (net (code "59") (name "PHOTO_TRANS") (class "Default")
      (node (ref "R46") (pin "2") (pinfunction "2_2") (pintype "passive"))
      (node (ref "U3") (pin "13") (pinfunction "PB1(OC1A)_13") (pintype "bidirectional"))
    )
    (net (code "60") (name "RESET") (class "Default")
      (node (ref "POGO_PALACE") (pin "6") (pinfunction "6_6") (pintype "passive"))
      (node (ref "R18") (pin "1") (pinfunction "1_1") (pintype "passive"))
      (node (ref "U3") (pin "29") (pinfunction "PC6(/RESET)_29") (pintype "bidirectional"))
    )
    (net (code "61") (name "SCK") (class "Default")
      (node (ref "IC1") (pin "3") (pinfunction "SCK_3") (pintype "input"))
      (node (ref "POGO_PALACE") (pin "4") (pinfunction "4_4") (pintype "passive"))
      (node (ref "U3") (pin "17") (pinfunction "PB5(SCK)_17") (pintype "bidirectional"))
    )
    (net (code "62") (name "SCL") (class "Default")
      (node (ref "U3") (pin "28") (pinfunction "PC5(ADC5/SCL)_28") (pintype "bidirectional"))
    )
    (net (code "63") (name "SDA") (class "Default")
      (node (ref "U3") (pin "27") (pinfunction "PC4(ADC4/SDA)_27") (pintype "bidirectional"))
    )
    (net (code "64") (name "TAPTEMPO") (class "Default")
      (node (ref "ONOFF4") (pin "MP") (pinfunction "MP_MP") (pintype "passive"))
      (node (ref "U3") (pin "2") (pinfunction "PD4(XCK/T0)_2") (pintype "bidirectional"))
    )
    (net (code "65") (name "VB") (class "Default")
      (node (ref "C10") (pin "-") (pinfunction "-_-") (pintype "passive"))
      (node (ref "C11") (pin "+") (pinfunction "+_+") (pintype "passive"))
      (node (ref "IC2") (pin "3") (pinfunction "+IN_3") (pintype "input"))
      (node (ref "IC2") (pin "6") (pinfunction "-IN_6") (pintype "input"))
      (node (ref "IC2") (pin "7") (pinfunction "OUT_7") (pintype "output"))
      (node (ref "R19") (pin "2") (pinfunction "2_2") (pintype "passive"))
      (node (ref "R3") (pin "2") (pinfunction "2_2") (pintype "passive"))
      (node (ref "U1") (pin "3") (pinfunction "EC-_3") (pintype "output"))
      (node (ref "U1") (pin "6") (pinfunction "GND_6") (pintype "passive"))
      (node (ref "U2") (pin "5") (pinfunction "+IN2_5") (pintype "input"))
      (node (ref "VOL") (pin "P$1") (pinfunction "E_P$1") (pintype "passive"))
    )
    (net (code "66") (name "VCA_OUT") (class "Default")
      (node (ref "C3") (pin "1") (pinfunction "1_1") (pintype "passive"))
      (node (ref "R5") (pin "2") (pinfunction "2_2") (pintype "passive"))
      (node (ref "U1") (pin "8") (pinfunction "OUT_8") (pintype "output"))
      (node (ref "U2") (pin "6") (pinfunction "-IN2_6") (pintype "input"))
    )
    (net (code "67") (name "unconnected-(U3-ADC6-Pad19)") (class "Default")
      (node (ref "U3") (pin "19") (pinfunction "ADC6_19") (pintype "bidirectional"))
    )
    (net (code "68") (name "unconnected-(U3-ADC7-Pad22)") (class "Default")
      (node (ref "U3") (pin "22") (pinfunction "ADC7_22") (pintype "bidirectional"))
    )
    (net (code "69") (name "unconnected-(U3-PC3(ADC3)-Pad26)") (class "Default")
      (node (ref "U3") (pin "26") (pinfunction "PC3(ADC3)_26") (pintype "bidirectional"))
    )
    (net (code "70") (name "unconnected-(U3-PD5(T1)-Pad9)") (class "Default")
      (node (ref "U3") (pin "9") (pinfunction "PD5(T1)_9") (pintype "bidirectional"))
    )
  )
)
